# Interface_DigitalToCLP.net
KiCad netlist of a schematic drawn in Altium Designer
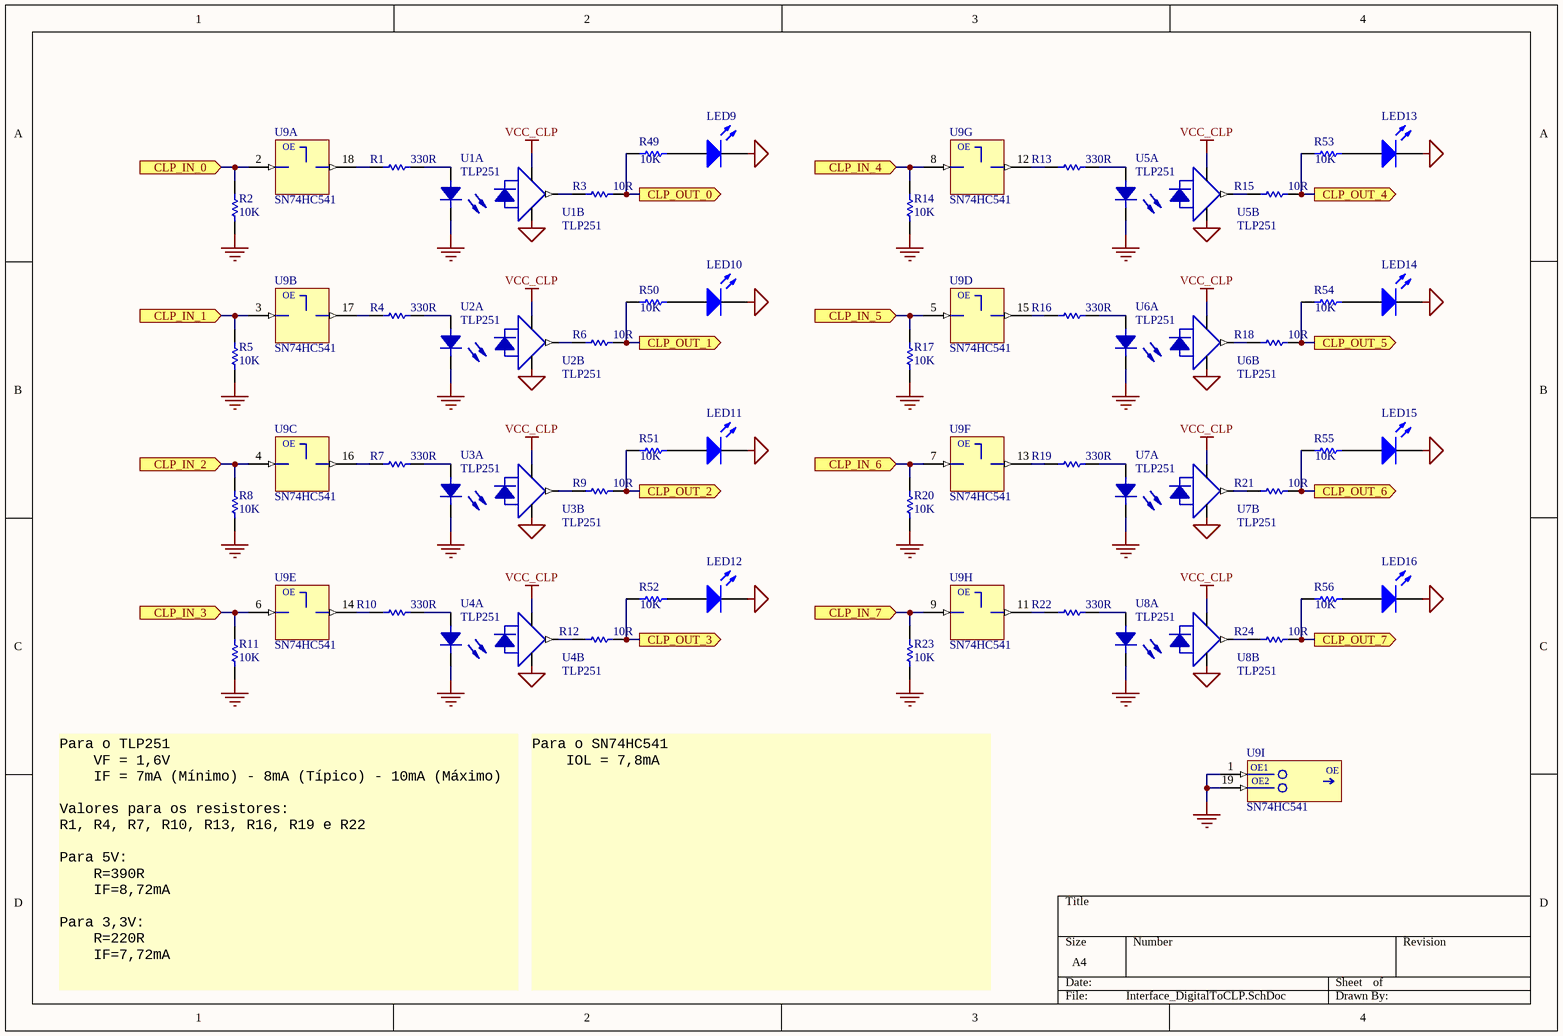
[diagram p0: Interface_DigitalToCLP.SchDoc]

(export (version "E")
  (design (tool "Eeschema 10.0.6"))
  (components
    (comp (ref "LED9")
      (value "151053YS04500")
      (footprint "Type 5mm")
      (description "THT LED round mono-color waterclear, WL-TMRW, Yellow")
      (fields (field (name "MANUFACTURER") "Wuerth Elektronik"))
      (libsource (lib "Altium Content Vault") (part "WE-LED_K1A2-2"))
    )
    (comp (ref "LED10")
      (value "151053YS04500")
      (footprint "Type 5mm")
      (description "THT LED round mono-color waterclear, WL-TMRW, Yellow")
      (fields (field (name "MANUFACTURER") "Wuerth Elektronik"))
      (libsource (lib "Altium Content Vault") (part "WE-LED_K1A2-2"))
    )
    (comp (ref "LED11")
      (value "151053YS04500")
      (footprint "Type 5mm")
      (description "THT LED round mono-color waterclear, WL-TMRW, Yellow")
      (fields (field (name "MANUFACTURER") "Wuerth Elektronik"))
      (libsource (lib "Altium Content Vault") (part "WE-LED_K1A2-2"))
    )
    (comp (ref "LED12")
      (value "151053YS04500")
      (footprint "Type 5mm")
      (description "THT LED round mono-color waterclear, WL-TMRW, Yellow")
      (fields (field (name "MANUFACTURER") "Wuerth Elektronik"))
      (libsource (lib "Altium Content Vault") (part "WE-LED_K1A2-2"))
    )
    (comp (ref "LED13")
      (value "151053YS04500")
      (footprint "Type 5mm")
      (description "THT LED round mono-color waterclear, WL-TMRW, Yellow")
      (fields (field (name "MANUFACTURER") "Wuerth Elektronik"))
      (libsource (lib "Altium Content Vault") (part "WE-LED_K1A2-2"))
    )
    (comp (ref "LED14")
      (value "151053YS04500")
      (footprint "Type 5mm")
      (description "THT LED round mono-color waterclear, WL-TMRW, Yellow")
      (fields (field (name "MANUFACTURER") "Wuerth Elektronik"))
      (libsource (lib "Altium Content Vault") (part "WE-LED_K1A2-2"))
    )
    (comp (ref "LED15")
      (value "151053YS04500")
      (footprint "Type 5mm")
      (description "THT LED round mono-color waterclear, WL-TMRW, Yellow")
      (fields (field (name "MANUFACTURER") "Wuerth Elektronik"))
      (libsource (lib "Altium Content Vault") (part "WE-LED_K1A2-2"))
    )
    (comp (ref "LED16")
      (value "151053YS04500")
      (footprint "Type 5mm")
      (description "THT LED round mono-color waterclear, WL-TMRW, Yellow")
      (fields (field (name "MANUFACTURER") "Wuerth Elektronik"))
      (libsource (lib "Altium Content Vault") (part "WE-LED_K1A2-2"))
    )
    (comp (ref "R1")
      (value "330R")
      (footprint "CR25")
      (description "Resistor")
      (libsource (lib "Basic") (part "Resistor"))
    )
    (comp (ref "R2")
      (value "10K")
      (footprint "CR25")
      (description "Resistor")
      (libsource (lib "Basic") (part "Resistor"))
    )
    (comp (ref "R3")
      (value "10R")
      (footprint "CR25")
      (description "Resistor")
      (libsource (lib "Basic") (part "Resistor"))
    )
    (comp (ref "R4")
      (value "330R")
      (footprint "CR25")
      (description "Resistor")
      (libsource (lib "Basic") (part "Resistor"))
    )
    (comp (ref "R5")
      (value "10K")
      (footprint "CR25")
      (description "Resistor")
      (libsource (lib "Basic") (part "Resistor"))
    )
    (comp (ref "R6")
      (value "10R")
      (footprint "CR25")
      (description "Resistor")
      (libsource (lib "Basic") (part "Resistor"))
    )
    (comp (ref "R7")
      (value "330R")
      (footprint "CR25")
      (description "Resistor")
      (libsource (lib "Basic") (part "Resistor"))
    )
    (comp (ref "R8")
      (value "10K")
      (footprint "CR25")
      (description "Resistor")
      (libsource (lib "Basic") (part "Resistor"))
    )
    (comp (ref "R9")
      (value "10R")
      (footprint "CR25")
      (description "Resistor")
      (libsource (lib "Basic") (part "Resistor"))
    )
    (comp (ref "R10")
      (value "330R")
      (footprint "CR25")
      (description "Resistor")
      (libsource (lib "Basic") (part "Resistor"))
    )
    (comp (ref "R11")
      (value "10K")
      (footprint "CR25")
      (description "Resistor")
      (libsource (lib "Basic") (part "Resistor"))
    )
    (comp (ref "R12")
      (value "10R")
      (footprint "CR25")
      (description "Resistor")
      (libsource (lib "Basic") (part "Resistor"))
    )
    (comp (ref "R13")
      (value "330R")
      (footprint "CR25")
      (description "Resistor")
      (libsource (lib "Basic") (part "Resistor"))
    )
    (comp (ref "R14")
      (value "10K")
      (footprint "CR25")
      (description "Resistor")
      (libsource (lib "Basic") (part "Resistor"))
    )
    (comp (ref "R15")
      (value "10R")
      (footprint "CR25")
      (description "Resistor")
      (libsource (lib "Basic") (part "Resistor"))
    )
    (comp (ref "R16")
      (value "330R")
      (footprint "CR25")
      (description "Resistor")
      (libsource (lib "Basic") (part "Resistor"))
    )
    (comp (ref "R17")
      (value "10K")
      (footprint "CR25")
      (description "Resistor")
      (libsource (lib "Basic") (part "Resistor"))
    )
    (comp (ref "R18")
      (value "10R")
      (footprint "CR25")
      (description "Resistor")
      (libsource (lib "Basic") (part "Resistor"))
    )
    (comp (ref "R19")
      (value "330R")
      (footprint "CR25")
      (description "Resistor")
      (libsource (lib "Basic") (part "Resistor"))
    )
    (comp (ref "R20")
      (value "10K")
      (footprint "CR25")
      (description "Resistor")
      (libsource (lib "Basic") (part "Resistor"))
    )
    (comp (ref "R21")
      (value "10R")
      (footprint "CR25")
      (description "Resistor")
      (libsource (lib "Basic") (part "Resistor"))
    )
    (comp (ref "R22")
      (value "330R")
      (footprint "CR25")
      (description "Resistor")
      (libsource (lib "Basic") (part "Resistor"))
    )
    (comp (ref "R23")
      (value "10K")
      (footprint "CR25")
      (description "Resistor")
      (libsource (lib "Basic") (part "Resistor"))
    )
    (comp (ref "R24")
      (value "10R")
      (footprint "CR25")
      (description "Resistor")
      (libsource (lib "Basic") (part "Resistor"))
    )
    (comp (ref "R49")
      (value "10K")
      (footprint "AXIAL-0.3")
      (description "Resistor")
      (fields (field (name "Comment") "Res1") (field (name "PUBLISHER") "Altium Limited"))
      (libsource (lib "Miscellaneous Devices") (part "Res1"))
    )
    (comp (ref "R50")
      (value "10K")
      (footprint "AXIAL-0.3")
      (description "Resistor")
      (fields (field (name "Comment") "Res1") (field (name "PUBLISHER") "Altium Limited"))
      (libsource (lib "Miscellaneous Devices") (part "Res1"))
    )
    (comp (ref "R51")
      (value "10K")
      (footprint "AXIAL-0.3")
      (description "Resistor")
      (fields (field (name "Comment") "Res1") (field (name "PUBLISHER") "Altium Limited"))
      (libsource (lib "Miscellaneous Devices") (part "Res1"))
    )
    (comp (ref "R52")
      (value "10K")
      (footprint "AXIAL-0.3")
      (description "Resistor")
      (fields (field (name "Comment") "Res1") (field (name "PUBLISHER") "Altium Limited"))
      (libsource (lib "Miscellaneous Devices") (part "Res1"))
    )
    (comp (ref "R53")
      (value "10K")
      (footprint "AXIAL-0.3")
      (description "Resistor")
      (fields (field (name "Comment") "Res1") (field (name "PUBLISHER") "Altium Limited"))
      (libsource (lib "Miscellaneous Devices") (part "Res1"))
    )
    (comp (ref "R54")
      (value "10K")
      (footprint "AXIAL-0.3")
      (description "Resistor")
      (fields (field (name "Comment") "Res1") (field (name "PUBLISHER") "Altium Limited"))
      (libsource (lib "Miscellaneous Devices") (part "Res1"))
    )
    (comp (ref "R55")
      (value "10K")
      (footprint "AXIAL-0.3")
      (description "Resistor")
      (fields (field (name "Comment") "Res1") (field (name "PUBLISHER") "Altium Limited"))
      (libsource (lib "Miscellaneous Devices") (part "Res1"))
    )
    (comp (ref "R56")
      (value "10K")
      (footprint "AXIAL-0.3")
      (description "Resistor")
      (fields (field (name "Comment") "Res1") (field (name "PUBLISHER") "Altium Limited"))
      (libsource (lib "Miscellaneous Devices") (part "Res1"))
    )
    (comp (ref "U1")
      (value "TLP251")
      (footprint "DIP8")
      (description "Photocoupler")
      (libsource (lib "Toshiba") (part "TLP251"))
    )
    (comp (ref "U2")
      (value "TLP251")
      (footprint "DIP8")
      (description "Photocoupler")
      (libsource (lib "Toshiba") (part "TLP251"))
    )
    (comp (ref "U3")
      (value "TLP251")
      (footprint "DIP8")
      (description "Photocoupler")
      (libsource (lib "Toshiba") (part "TLP251"))
    )
    (comp (ref "U4")
      (value "TLP251")
      (footprint "DIP8")
      (description "Photocoupler")
      (libsource (lib "Toshiba") (part "TLP251"))
    )
    (comp (ref "U5")
      (value "TLP251")
      (footprint "DIP8")
      (description "Photocoupler")
      (libsource (lib "Toshiba") (part "TLP251"))
    )
    (comp (ref "U6")
      (value "TLP251")
      (footprint "DIP8")
      (description "Photocoupler")
      (libsource (lib "Toshiba") (part "TLP251"))
    )
    (comp (ref "U7")
      (value "TLP251")
      (footprint "DIP8")
      (description "Photocoupler")
      (libsource (lib "Toshiba") (part "TLP251"))
    )
    (comp (ref "U8")
      (value "TLP251")
      (footprint "DIP8")
      (description "Photocoupler")
      (libsource (lib "Toshiba") (part "TLP251"))
    )
    (comp (ref "U9")
      (value "SN74HC541")
      (footprint "PDIP20")
      (description "Octal Buffers and Line Drivers With 3-State Outputs")
      (libsource (lib "Texas Instruments") (part "SN74HC541"))
    )
  )
  (nets
    (net (code "1") (name "/CLP_IN_0") (class "Default")
      (node (ref "R2") (pin "2") (pinfunction "2_2") (pintype "passive"))
      (node (ref "U9") (pin "2") (pinfunction "A1_2") (pintype "input"))
    )
    (net (code "2") (name "/CLP_IN_1") (class "Default")
      (node (ref "R5") (pin "2") (pinfunction "2_2") (pintype "passive"))
      (node (ref "U9") (pin "3") (pinfunction "A2_3") (pintype "input"))
    )
    (net (code "3") (name "/CLP_IN_2") (class "Default")
      (node (ref "R8") (pin "2") (pinfunction "2_2") (pintype "passive"))
      (node (ref "U9") (pin "4") (pinfunction "A3_4") (pintype "input"))
    )
    (net (code "4") (name "/CLP_IN_3") (class "Default")
      (node (ref "R11") (pin "2") (pinfunction "2_2") (pintype "passive"))
      (node (ref "U9") (pin "6") (pinfunction "A5_6") (pintype "input"))
    )
    (net (code "5") (name "/CLP_IN_4") (class "Default")
      (node (ref "R14") (pin "2") (pinfunction "2_2") (pintype "passive"))
      (node (ref "U9") (pin "8") (pinfunction "A7_8") (pintype "input"))
    )
    (net (code "6") (name "/CLP_IN_5") (class "Default")
      (node (ref "R17") (pin "2") (pinfunction "2_2") (pintype "passive"))
      (node (ref "U9") (pin "5") (pinfunction "A4_5") (pintype "input"))
    )
    (net (code "7") (name "/CLP_IN_6") (class "Default")
      (node (ref "R20") (pin "2") (pinfunction "2_2") (pintype "passive"))
      (node (ref "U9") (pin "7") (pinfunction "A6_7") (pintype "input"))
    )
    (net (code "8") (name "/CLP_IN_7") (class "Default")
      (node (ref "R23") (pin "2") (pinfunction "2_2") (pintype "passive"))
      (node (ref "U9") (pin "9") (pinfunction "A8_9") (pintype "input"))
    )
    (net (code "9") (name "/CLP_OUT_0") (class "Default")
      (node (ref "R3") (pin "2") (pinfunction "2_2") (pintype "passive"))
      (node (ref "R49") (pin "2") (pinfunction "2_2") (pintype "passive"))
    )
    (net (code "10") (name "/CLP_OUT_1") (class "Default")
      (node (ref "R50") (pin "2") (pinfunction "2_2") (pintype "passive"))
      (node (ref "R6") (pin "2") (pinfunction "2_2") (pintype "passive"))
    )
    (net (code "11") (name "/CLP_OUT_2") (class "Default")
      (node (ref "R51") (pin "2") (pinfunction "2_2") (pintype "passive"))
      (node (ref "R9") (pin "2") (pinfunction "2_2") (pintype "passive"))
    )
    (net (code "12") (name "/CLP_OUT_3") (class "Default")
      (node (ref "R12") (pin "2") (pinfunction "2_2") (pintype "passive"))
      (node (ref "R52") (pin "2") (pinfunction "2_2") (pintype "passive"))
    )
    (net (code "13") (name "/CLP_OUT_4") (class "Default")
      (node (ref "R15") (pin "2") (pinfunction "2_2") (pintype "passive"))
      (node (ref "R53") (pin "2") (pinfunction "2_2") (pintype "passive"))
    )
    (net (code "14") (name "/CLP_OUT_5") (class "Default")
      (node (ref "R18") (pin "2") (pinfunction "2_2") (pintype "passive"))
      (node (ref "R54") (pin "2") (pinfunction "2_2") (pintype "passive"))
    )
    (net (code "15") (name "/CLP_OUT_6") (class "Default")
      (node (ref "R21") (pin "2") (pinfunction "2_2") (pintype "passive"))
      (node (ref "R55") (pin "2") (pinfunction "2_2") (pintype "passive"))
    )
    (net (code "16") (name "/CLP_OUT_7") (class "Default")
      (node (ref "R24") (pin "2") (pinfunction "2_2") (pintype "passive"))
      (node (ref "R56") (pin "2") (pinfunction "2_2") (pintype "passive"))
    )
    (net (code "17") (name "CLP_GND") (class "Default")
      (node (ref "LED10") (pin "1") (pinfunction "K_1") (pintype "passive"))
      (node (ref "LED11") (pin "1") (pinfunction "K_1") (pintype "passive"))
      (node (ref "LED12") (pin "1") (pinfunction "K_1") (pintype "passive"))
      (node (ref "LED13") (pin "1") (pinfunction "K_1") (pintype "passive"))
      (node (ref "LED14") (pin "1") (pinfunction "K_1") (pintype "passive"))
      (node (ref "LED15") (pin "1") (pinfunction "K_1") (pintype "passive"))
      (node (ref "LED16") (pin "1") (pinfunction "K_1") (pintype "passive"))
      (node (ref "LED9") (pin "1") (pinfunction "K_1") (pintype "passive"))
      (node (ref "U1") (pin "5") (pinfunction "5_5") (pintype "power_in"))
      (node (ref "U2") (pin "5") (pinfunction "5_5") (pintype "power_in"))
      (node (ref "U3") (pin "5") (pinfunction "5_5") (pintype "power_in"))
      (node (ref "U4") (pin "5") (pinfunction "5_5") (pintype "power_in"))
      (node (ref "U5") (pin "5") (pinfunction "5_5") (pintype "power_in"))
      (node (ref "U6") (pin "5") (pinfunction "5_5") (pintype "power_in"))
      (node (ref "U7") (pin "5") (pinfunction "5_5") (pintype "power_in"))
      (node (ref "U8") (pin "5") (pinfunction "5_5") (pintype "power_in"))
    )
    (net (code "18") (name "GND") (class "Default")
      (node (ref "R11") (pin "1") (pinfunction "1_1") (pintype "passive"))
      (node (ref "R14") (pin "1") (pinfunction "1_1") (pintype "passive"))
      (node (ref "R17") (pin "1") (pinfunction "1_1") (pintype "passive"))
      (node (ref "R2") (pin "1") (pinfunction "1_1") (pintype "passive"))
      (node (ref "R20") (pin "1") (pinfunction "1_1") (pintype "passive"))
      (node (ref "R23") (pin "1") (pinfunction "1_1") (pintype "passive"))
      (node (ref "R5") (pin "1") (pinfunction "1_1") (pintype "passive"))
      (node (ref "R8") (pin "1") (pinfunction "1_1") (pintype "passive"))
      (node (ref "U1") (pin "3") (pinfunction "3_3") (pintype "passive"))
      (node (ref "U2") (pin "3") (pinfunction "3_3") (pintype "passive"))
      (node (ref "U3") (pin "3") (pinfunction "3_3") (pintype "passive"))
      (node (ref "U4") (pin "3") (pinfunction "3_3") (pintype "passive"))
      (node (ref "U5") (pin "3") (pinfunction "3_3") (pintype "passive"))
      (node (ref "U6") (pin "3") (pinfunction "3_3") (pintype "passive"))
      (node (ref "U7") (pin "3") (pinfunction "3_3") (pintype "passive"))
      (node (ref "U8") (pin "3") (pinfunction "3_3") (pintype "passive"))
      (node (ref "U9") (pin "1") (pinfunction "OE1_1") (pintype "input"))
      (node (ref "U9") (pin "19") (pinfunction "OE2_19") (pintype "input"))
    )
    (net (code "19") (name "Net-(LED9-A)") (class "Default")
      (node (ref "LED9") (pin "2") (pinfunction "A_2") (pintype "passive"))
      (node (ref "R49") (pin "1") (pinfunction "1_1") (pintype "passive"))
    )
    (net (code "20") (name "Net-(LED10-A)") (class "Default")
      (node (ref "LED10") (pin "2") (pinfunction "A_2") (pintype "passive"))
      (node (ref "R50") (pin "1") (pinfunction "1_1") (pintype "passive"))
    )
    (net (code "21") (name "Net-(LED11-A)") (class "Default")
      (node (ref "LED11") (pin "2") (pinfunction "A_2") (pintype "passive"))
      (node (ref "R51") (pin "1") (pinfunction "1_1") (pintype "passive"))
    )
    (net (code "22") (name "Net-(LED12-A)") (class "Default")
      (node (ref "LED12") (pin "2") (pinfunction "A_2") (pintype "passive"))
      (node (ref "R52") (pin "1") (pinfunction "1_1") (pintype "passive"))
    )
    (net (code "23") (name "Net-(LED13-A)") (class "Default")
      (node (ref "LED13") (pin "2") (pinfunction "A_2") (pintype "passive"))
      (node (ref "R53") (pin "1") (pinfunction "1_1") (pintype "passive"))
    )
    (net (code "24") (name "Net-(LED14-A)") (class "Default")
      (node (ref "LED14") (pin "2") (pinfunction "A_2") (pintype "passive"))
      (node (ref "R54") (pin "1") (pinfunction "1_1") (pintype "passive"))
    )
    (net (code "25") (name "Net-(LED15-A)") (class "Default")
      (node (ref "LED15") (pin "2") (pinfunction "A_2") (pintype "passive"))
      (node (ref "R55") (pin "1") (pinfunction "1_1") (pintype "passive"))
    )
    (net (code "26") (name "Net-(LED16-A)") (class "Default")
      (node (ref "LED16") (pin "2") (pinfunction "A_2") (pintype "passive"))
      (node (ref "R56") (pin "1") (pinfunction "1_1") (pintype "passive"))
    )
    (net (code "27") (name "Net-(R1-Pad2)") (class "Default")
      (node (ref "R1") (pin "2") (pinfunction "2_2") (pintype "passive"))
      (node (ref "U1") (pin "2") (pinfunction "2_2") (pintype "passive"))
    )
    (net (code "28") (name "Net-(R3-Pad1)") (class "Default")
      (node (ref "R3") (pin "1") (pinfunction "1_1") (pintype "passive"))
      (node (ref "U1") (pin "6") (pinfunction "6_6") (pintype "output"))
    )
    (net (code "29") (name "Net-(R4-Pad2)") (class "Default")
      (node (ref "R4") (pin "2") (pinfunction "2_2") (pintype "passive"))
      (node (ref "U2") (pin "2") (pinfunction "2_2") (pintype "passive"))
    )
    (net (code "30") (name "Net-(R6-Pad1)") (class "Default")
      (node (ref "R6") (pin "1") (pinfunction "1_1") (pintype "passive"))
      (node (ref "U2") (pin "6") (pinfunction "6_6") (pintype "output"))
    )
    (net (code "31") (name "Net-(R7-Pad2)") (class "Default")
      (node (ref "R7") (pin "2") (pinfunction "2_2") (pintype "passive"))
      (node (ref "U3") (pin "2") (pinfunction "2_2") (pintype "passive"))
    )
    (net (code "32") (name "Net-(R9-Pad1)") (class "Default")
      (node (ref "R9") (pin "1") (pinfunction "1_1") (pintype "passive"))
      (node (ref "U3") (pin "6") (pinfunction "6_6") (pintype "output"))
    )
    (net (code "33") (name "Net-(R10-Pad2)") (class "Default")
      (node (ref "R10") (pin "2") (pinfunction "2_2") (pintype "passive"))
      (node (ref "U4") (pin "2") (pinfunction "2_2") (pintype "passive"))
    )
    (net (code "34") (name "Net-(R12-Pad1)") (class "Default")
      (node (ref "R12") (pin "1") (pinfunction "1_1") (pintype "passive"))
      (node (ref "U4") (pin "6") (pinfunction "6_6") (pintype "output"))
    )
    (net (code "35") (name "Net-(R13-Pad2)") (class "Default")
      (node (ref "R13") (pin "2") (pinfunction "2_2") (pintype "passive"))
      (node (ref "U5") (pin "2") (pinfunction "2_2") (pintype "passive"))
    )
    (net (code "36") (name "Net-(R15-Pad1)") (class "Default")
      (node (ref "R15") (pin "1") (pinfunction "1_1") (pintype "passive"))
      (node (ref "U5") (pin "6") (pinfunction "6_6") (pintype "output"))
    )
    (net (code "37") (name "Net-(R16-Pad2)") (class "Default")
      (node (ref "R16") (pin "2") (pinfunction "2_2") (pintype "passive"))
      (node (ref "U6") (pin "2") (pinfunction "2_2") (pintype "passive"))
    )
    (net (code "38") (name "Net-(R18-Pad1)") (class "Default")
      (node (ref "R18") (pin "1") (pinfunction "1_1") (pintype "passive"))
      (node (ref "U6") (pin "6") (pinfunction "6_6") (pintype "output"))
    )
    (net (code "39") (name "Net-(R19-Pad2)") (class "Default")
      (node (ref "R19") (pin "2") (pinfunction "2_2") (pintype "passive"))
      (node (ref "U7") (pin "2") (pinfunction "2_2") (pintype "passive"))
    )
    (net (code "40") (name "Net-(R21-Pad1)") (class "Default")
      (node (ref "R21") (pin "1") (pinfunction "1_1") (pintype "passive"))
      (node (ref "U7") (pin "6") (pinfunction "6_6") (pintype "output"))
    )
    (net (code "41") (name "Net-(R22-Pad2)") (class "Default")
      (node (ref "R22") (pin "2") (pinfunction "2_2") (pintype "passive"))
      (node (ref "U8") (pin "2") (pinfunction "2_2") (pintype "passive"))
    )
    (net (code "42") (name "Net-(R24-Pad1)") (class "Default")
      (node (ref "R24") (pin "1") (pinfunction "1_1") (pintype "passive"))
      (node (ref "U8") (pin "6") (pinfunction "6_6") (pintype "output"))
    )
    (net (code "43") (name "Net-(U9A-Y1)") (class "Default")
      (node (ref "R1") (pin "1") (pinfunction "1_1") (pintype "passive"))
      (node (ref "U9") (pin "18") (pinfunction "Y1_18") (pintype "output"))
    )
    (net (code "44") (name "Net-(U9B-Y2)") (class "Default")
      (node (ref "R4") (pin "1") (pinfunction "1_1") (pintype "passive"))
      (node (ref "U9") (pin "17") (pinfunction "Y2_17") (pintype "output"))
    )
    (net (code "45") (name "Net-(U9C-Y3)") (class "Default")
      (node (ref "R7") (pin "1") (pinfunction "1_1") (pintype "passive"))
      (node (ref "U9") (pin "16") (pinfunction "Y3_16") (pintype "output"))
    )
    (net (code "46") (name "Net-(U9D-Y4)") (class "Default")
      (node (ref "R16") (pin "1") (pinfunction "1_1") (pintype "passive"))
      (node (ref "U9") (pin "15") (pinfunction "Y4_15") (pintype "output"))
    )
    (net (code "47") (name "Net-(U9E-Y5)") (class "Default")
      (node (ref "R10") (pin "1") (pinfunction "1_1") (pintype "passive"))
      (node (ref "U9") (pin "14") (pinfunction "Y5_14") (pintype "output"))
    )
    (net (code "48") (name "Net-(U9F-Y6)") (class "Default")
      (node (ref "R19") (pin "1") (pinfunction "1_1") (pintype "passive"))
      (node (ref "U9") (pin "13") (pinfunction "Y6_13") (pintype "output"))
    )
    (net (code "49") (name "Net-(U9G-Y7)") (class "Default")
      (node (ref "R13") (pin "1") (pinfunction "1_1") (pintype "passive"))
      (node (ref "U9") (pin "12") (pinfunction "Y7_12") (pintype "output"))
    )
    (net (code "50") (name "Net-(U9H-Y8)") (class "Default")
      (node (ref "R22") (pin "1") (pinfunction "1_1") (pintype "passive"))
      (node (ref "U9") (pin "11") (pinfunction "Y8_11") (pintype "output"))
    )
    (net (code "51") (name "VCC_CLP") (class "Default")
      (node (ref "U1") (pin "8") (pinfunction "8_8") (pintype "power_in"))
      (node (ref "U2") (pin "8") (pinfunction "8_8") (pintype "power_in"))
      (node (ref "U3") (pin "8") (pinfunction "8_8") (pintype "power_in"))
      (node (ref "U4") (pin "8") (pinfunction "8_8") (pintype "power_in"))
      (node (ref "U5") (pin "8") (pinfunction "8_8") (pintype "power_in"))
      (node (ref "U6") (pin "8") (pinfunction "8_8") (pintype "power_in"))
      (node (ref "U7") (pin "8") (pinfunction "8_8") (pintype "power_in"))
      (node (ref "U8") (pin "8") (pinfunction "8_8") (pintype "power_in"))
    )
  )
)
